# BalanceCar_CCD_Base.net
KiCad netlist of a schematic drawn in Altium Designer
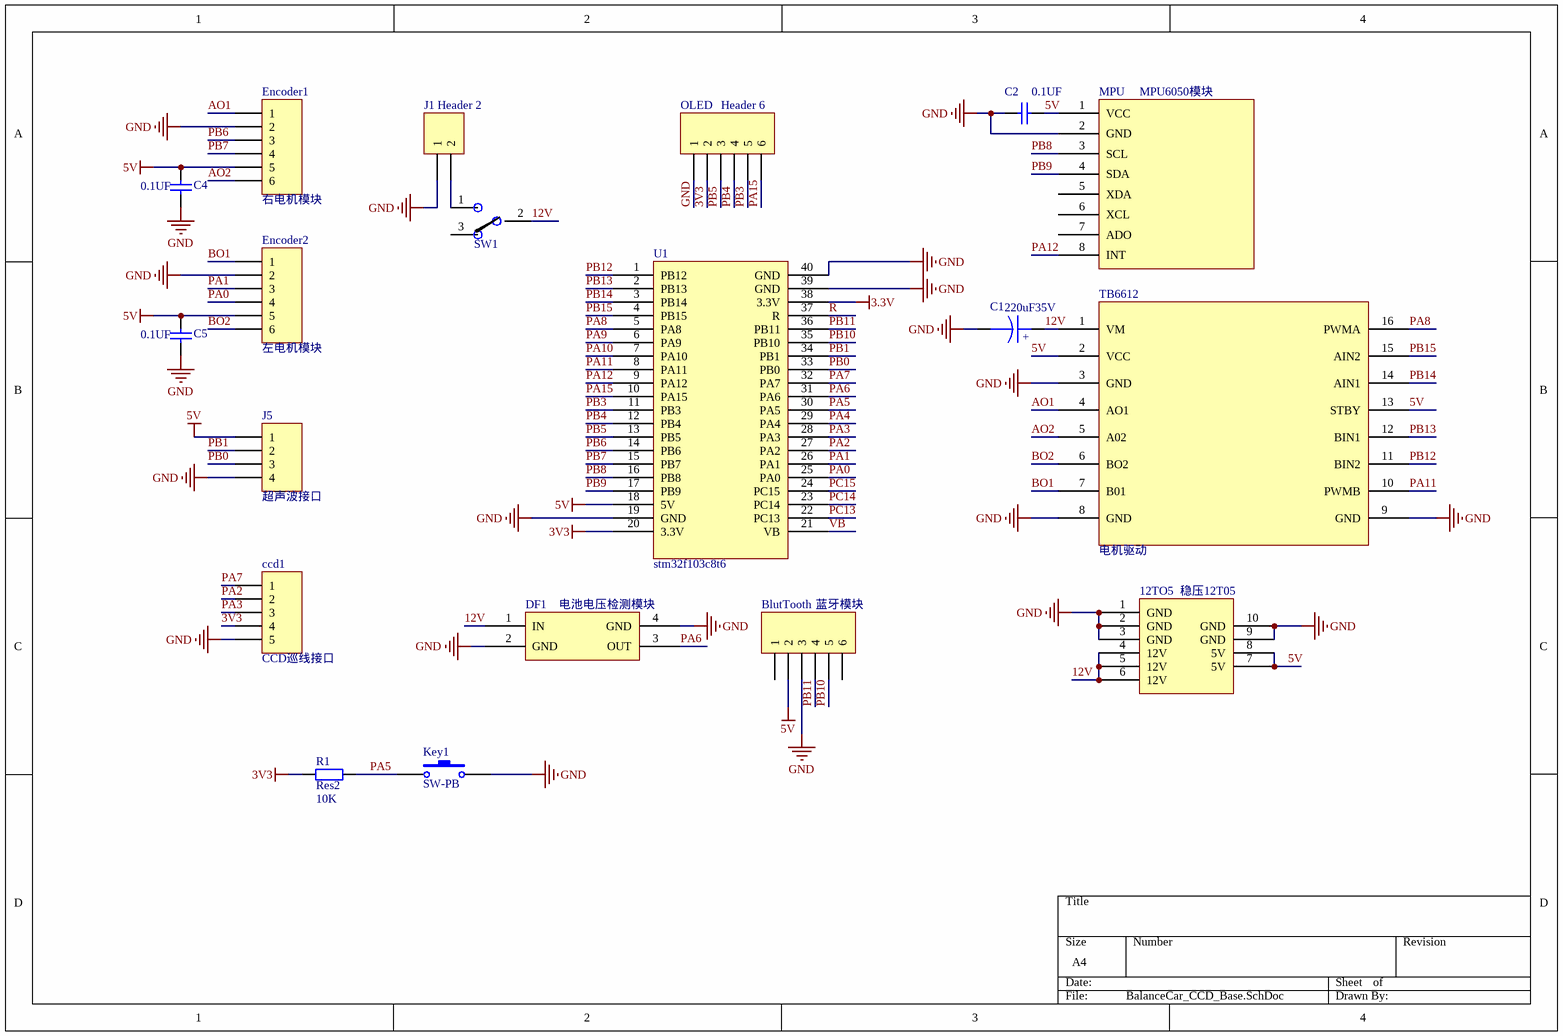
[diagram p0: BalanceCar_CCD_Base.SchDoc]

(export (version "E")
  (design (tool "Eeschema 10.0.6"))
  (components
    (comp (ref "12TO5")
      (value "稳压12T05")
      (footprint "稳压12T05")
      (libsource (lib "BalanceCar") (part "稳压12T05"))
    )
    (comp (ref "BlutTooth")
      (value "蓝牙模块")
      (footprint "HDR1X6 - XH弯")
      (description "不用焊")
      (fields (field (name "PUBLISHER") "Altium Limited"))
      (libsource (lib "BalanceCar") (part "Header 6"))
    )
    (comp (ref "C1")
      (value "220uF35V")
      (footprint "CAP-820uF-6.3V")
      (description "Capacitor")
      (libsource (lib "BalanceCar") (part "CAPACITOR POL"))
    )
    (comp (ref "C2")
      (value "0.1UF")
      (footprint "Cap-CP")
      (description "Capacitor")
      (fields (field (name "PUBLISHER") "Altium Limited"))
      (libsource (lib "BalanceCar") (part "Cap"))
    )
    (comp (ref "C4")
      (value "0.1UF")
      (footprint "Cap-CP")
      (description "Capacitor")
      (fields (field (name "PUBLISHER") "Altium Limited"))
      (libsource (lib "BalanceCar") (part "Cap"))
    )
    (comp (ref "C5")
      (value "0.1UF")
      (footprint "Cap-CP")
      (description "Capacitor")
      (fields (field (name "PUBLISHER") "Altium Limited"))
      (libsource (lib "BalanceCar") (part "Cap"))
    )
    (comp (ref "ccd1")
      (value "CCD巡线接口")
      (footprint "CCD5")
      (description "Header, 5-Pin")
      (fields (field (name "PUBLISHER") "Altium Limited"))
      (libsource (lib "Miscellaneous Connectors") (part "Header 5"))
    )
    (comp (ref "DF1")
      (value "电池电压检测模块")
      (footprint "DF - 2")
      (libsource (lib "BalanceCar") (part "电阻分压测量电量"))
    )
    (comp (ref "Encoder1")
      (value "右电机模块")
      (footprint "HDR1X6 - XH弯")
      (description "不用焊")
      (fields (field (name "PUBLISHER") "Altium Limited"))
      (libsource (lib "") (part "Header 6_1"))
    )
    (comp (ref "Encoder2")
      (value "左电机模块")
      (footprint "HDR1X6 - XH弯")
      (description "不用焊")
      (fields (field (name "PUBLISHER") "Altium Limited"))
      (libsource (lib "") (part "Header 6_1"))
    )
    (comp (ref "J1")
      (value "Header 2")
      (footprint "T HEAD")
      (description "Header, 2-Pin")
      (fields (field (name "PUBLISHER") "Altium Limited"))
      (libsource (lib "BalanceCar") (part "Header 2"))
    )
    (comp (ref "J5")
      (value "超声波接口")
      (footprint "HDR1X4")
      (description "Header, 4-Pin")
      (fields (field (name "PUBLISHER") "Altium Limited"))
      (libsource (lib "BalanceCar") (part "Header 4"))
    )
    (comp (ref "Key1")
      (value "SW-PB")
      (footprint "KEY")
      (description "Switch")
      (fields (field (name "PUBLISHER") "Altium Limited"))
      (libsource (lib "Miscellaneous Devices") (part "SW-PB"))
    )
    (comp (ref "MPU")
      (value "MPU6050模块")
      (footprint "6050new")
      (libsource (lib "BalanceCar") (part "MPU6050模块"))
    )
    (comp (ref "OLED")
      (value "Header 6")
      (footprint "OLED6")
      (description "Header, 6-Pin")
      (fields (field (name "PUBLISHER") "Altium Limited"))
      (libsource (lib "Miscellaneous Connectors") (part "Header 6"))
    )
    (comp (ref "R1")
      (value "Res2")
      (footprint "AXIAL-0.4")
      (description "Resistor")
      (fields (field (name "ALTIUM_VALUE") "10K") (field (name "PUBLISHER") "Altium Limited"))
      (libsource (lib "Miscellaneous Devices") (part "Res2"))
    )
    (comp (ref "SW1")
      (value "SW-SPDT")
      (footprint "SS12d11拨动电源开关")
      (description "单刀双掷开关")
      (libsource (lib "BalanceCar") (part "SW-SPDT"))
    )
    (comp (ref "TB6612")
      (value "电机驱动")
      (footprint "TB6612DIP")
      (libsource (lib "BalanceCar") (part "TB6612"))
    )
    (comp (ref "U1")
      (value "stm32f103c8t6")
      (footprint "PCBComponent_1 - duplicate")
      (libsource (lib "PCB_Project1") (part "Component_1_1"))
    )
  )
  (nets
    (net (code "1") (name "/12V") (class "Default")
      (node (ref "12TO5") (pin "4") (pinfunction "12V_4") (pintype "passive"))
      (node (ref "12TO5") (pin "5") (pinfunction "12V_5") (pintype "passive"))
      (node (ref "12TO5") (pin "6") (pinfunction "12V_6") (pintype "passive"))
      (node (ref "C1") (pin "1") (pinfunction "1_1") (pintype "passive"))
      (node (ref "DF1") (pin "1") (pinfunction "IN_1") (pintype "passive"))
      (node (ref "SW1") (pin "2") (pinfunction "2_2") (pintype "passive"))
      (node (ref "TB6612") (pin "1") (pinfunction "VM_1") (pintype "passive"))
    )
    (net (code "2") (name "/AO1") (class "Default")
      (node (ref "Encoder1") (pin "1") (pinfunction "1_1") (pintype "passive"))
      (node (ref "TB6612") (pin "4") (pinfunction "AO1_4") (pintype "passive"))
    )
    (net (code "3") (name "/AO2") (class "Default")
      (node (ref "Encoder1") (pin "6") (pinfunction "6_6") (pintype "passive"))
      (node (ref "TB6612") (pin "5") (pinfunction "A02_5") (pintype "passive"))
    )
    (net (code "4") (name "/BO1") (class "Default")
      (node (ref "Encoder2") (pin "1") (pinfunction "1_1") (pintype "passive"))
      (node (ref "TB6612") (pin "7") (pinfunction "B01_7") (pintype "passive"))
    )
    (net (code "5") (name "/BO2") (class "Default")
      (node (ref "Encoder2") (pin "6") (pinfunction "6_6") (pintype "passive"))
      (node (ref "TB6612") (pin "6") (pinfunction "BO2_6") (pintype "passive"))
    )
    (net (code "6") (name "/PA0") (class "Default")
      (node (ref "Encoder2") (pin "4") (pinfunction "4_4") (pintype "passive"))
      (node (ref "U1") (pin "25") (pinfunction "PA0_25") (pintype "passive"))
    )
    (net (code "7") (name "/PA1") (class "Default")
      (node (ref "Encoder2") (pin "3") (pinfunction "3_3") (pintype "passive"))
      (node (ref "U1") (pin "26") (pinfunction "PA1_26") (pintype "passive"))
    )
    (net (code "8") (name "/PA2") (class "Default")
      (node (ref "U1") (pin "27") (pinfunction "PA2_27") (pintype "passive"))
      (node (ref "ccd1") (pin "2") (pinfunction "2_2") (pintype "passive"))
    )
    (net (code "9") (name "/PA3") (class "Default")
      (node (ref "U1") (pin "28") (pinfunction "PA3_28") (pintype "passive"))
      (node (ref "ccd1") (pin "3") (pinfunction "3_3") (pintype "passive"))
    )
    (net (code "10") (name "/PA4") (class "Default")
      (node (ref "U1") (pin "29") (pinfunction "PA4_29") (pintype "passive"))
    )
    (net (code "11") (name "/PA5") (class "Default")
      (node (ref "Key1") (pin "1") (pinfunction "1_1") (pintype "passive"))
      (node (ref "R1") (pin "2") (pinfunction "2_2") (pintype "passive"))
      (node (ref "U1") (pin "30") (pinfunction "PA5_30") (pintype "passive"))
    )
    (net (code "12") (name "/PA6") (class "Default")
      (node (ref "DF1") (pin "3") (pinfunction "OUT_3") (pintype "passive"))
      (node (ref "U1") (pin "31") (pinfunction "PA6_31") (pintype "passive"))
    )
    (net (code "13") (name "/PA7") (class "Default")
      (node (ref "U1") (pin "32") (pinfunction "PA7_32") (pintype "passive"))
      (node (ref "ccd1") (pin "1") (pinfunction "1_1") (pintype "passive"))
    )
    (net (code "14") (name "/PA8") (class "Default")
      (node (ref "TB6612") (pin "16") (pinfunction "PWMA_16") (pintype "passive"))
      (node (ref "U1") (pin "5") (pinfunction "PA8_5") (pintype "passive"))
    )
    (net (code "15") (name "/PA9") (class "Default")
      (node (ref "U1") (pin "6") (pinfunction "PA9_6") (pintype "passive"))
    )
    (net (code "16") (name "/PA10") (class "Default")
      (node (ref "U1") (pin "7") (pinfunction "PA10_7") (pintype "passive"))
    )
    (net (code "17") (name "/PA11") (class "Default")
      (node (ref "TB6612") (pin "10") (pinfunction "PWMB_10") (pintype "passive"))
      (node (ref "U1") (pin "8") (pinfunction "PA11_8") (pintype "passive"))
    )
    (net (code "18") (name "/PA12") (class "Default")
      (node (ref "MPU") (pin "8") (pinfunction "INT_8") (pintype "passive"))
      (node (ref "U1") (pin "9") (pinfunction "PA12_9") (pintype "passive"))
    )
    (net (code "19") (name "/PA15") (class "Default")
      (node (ref "OLED") (pin "6") (pinfunction "6_6") (pintype "passive"))
      (node (ref "U1") (pin "10") (pinfunction "PA15_10") (pintype "passive"))
    )
    (net (code "20") (name "/PB0") (class "Default")
      (node (ref "J5") (pin "3") (pinfunction "3_3") (pintype "passive"))
      (node (ref "U1") (pin "33") (pinfunction "PB0_33") (pintype "passive"))
    )
    (net (code "21") (name "/PB1") (class "Default")
      (node (ref "J5") (pin "2") (pinfunction "2_2") (pintype "passive"))
      (node (ref "U1") (pin "34") (pinfunction "PB1_34") (pintype "passive"))
    )
    (net (code "22") (name "/PB3") (class "Default")
      (node (ref "OLED") (pin "5") (pinfunction "5_5") (pintype "passive"))
      (node (ref "U1") (pin "11") (pinfunction "PB3_11") (pintype "passive"))
    )
    (net (code "23") (name "/PB4") (class "Default")
      (node (ref "OLED") (pin "4") (pinfunction "4_4") (pintype "passive"))
      (node (ref "U1") (pin "12") (pinfunction "PB4_12") (pintype "passive"))
    )
    (net (code "24") (name "/PB5") (class "Default")
      (node (ref "OLED") (pin "3") (pinfunction "3_3") (pintype "passive"))
      (node (ref "U1") (pin "13") (pinfunction "PB5_13") (pintype "passive"))
    )
    (net (code "25") (name "/PB6") (class "Default")
      (node (ref "Encoder1") (pin "3") (pinfunction "3_3") (pintype "passive"))
      (node (ref "U1") (pin "14") (pinfunction "PB6_14") (pintype "passive"))
    )
    (net (code "26") (name "/PB7") (class "Default")
      (node (ref "Encoder1") (pin "4") (pinfunction "4_4") (pintype "passive"))
      (node (ref "U1") (pin "15") (pinfunction "PB7_15") (pintype "passive"))
    )
    (net (code "27") (name "/PB8") (class "Default")
      (node (ref "MPU") (pin "3") (pinfunction "SCL_3") (pintype "passive"))
      (node (ref "U1") (pin "16") (pinfunction "PB8_16") (pintype "passive"))
    )
    (net (code "28") (name "/PB9") (class "Default")
      (node (ref "MPU") (pin "4") (pinfunction "SDA_4") (pintype "passive"))
      (node (ref "U1") (pin "17") (pinfunction "PB9_17") (pintype "passive"))
    )
    (net (code "29") (name "/PB10") (class "Default")
      (node (ref "BlutTooth") (pin "5") (pinfunction "5_5") (pintype "passive"))
      (node (ref "U1") (pin "35") (pinfunction "PB10_35") (pintype "passive"))
    )
    (net (code "30") (name "/PB11") (class "Default")
      (node (ref "BlutTooth") (pin "4") (pinfunction "4_4") (pintype "passive"))
      (node (ref "U1") (pin "36") (pinfunction "PB11_36") (pintype "passive"))
    )
    (net (code "31") (name "/PB12") (class "Default")
      (node (ref "TB6612") (pin "11") (pinfunction "BIN2_11") (pintype "passive"))
      (node (ref "U1") (pin "1") (pinfunction "PB12_1") (pintype "passive"))
    )
    (net (code "32") (name "/PB13") (class "Default")
      (node (ref "TB6612") (pin "12") (pinfunction "BIN1_12") (pintype "passive"))
      (node (ref "U1") (pin "2") (pinfunction "PB13_2") (pintype "passive"))
    )
    (net (code "33") (name "/PB14") (class "Default")
      (node (ref "TB6612") (pin "14") (pinfunction "AIN1_14") (pintype "passive"))
      (node (ref "U1") (pin "3") (pinfunction "PB14_3") (pintype "passive"))
    )
    (net (code "34") (name "/PB15") (class "Default")
      (node (ref "TB6612") (pin "15") (pinfunction "AIN2_15") (pintype "passive"))
      (node (ref "U1") (pin "4") (pinfunction "PB15_4") (pintype "passive"))
    )
    (net (code "35") (name "/PC13") (class "Default")
      (node (ref "U1") (pin "22") (pinfunction "PC13_22") (pintype "passive"))
    )
    (net (code "36") (name "/PC14") (class "Default")
      (node (ref "U1") (pin "23") (pinfunction "PC14_23") (pintype "passive"))
    )
    (net (code "37") (name "/PC15") (class "Default")
      (node (ref "U1") (pin "24") (pinfunction "PC15_24") (pintype "passive"))
    )
    (net (code "38") (name "/R") (class "Default")
      (node (ref "U1") (pin "37") (pinfunction "R_37") (pintype "passive"))
    )
    (net (code "39") (name "/VB") (class "Default")
      (node (ref "U1") (pin "21") (pinfunction "VB_21") (pintype "passive"))
    )
    (net (code "40") (name "3.3V") (class "Default")
      (node (ref "U1") (pin "38") (pinfunction "3.3V_38") (pintype "passive"))
    )
    (net (code "41") (name "3V3") (class "Default")
      (node (ref "OLED") (pin "2") (pinfunction "2_2") (pintype "passive"))
      (node (ref "R1") (pin "1") (pinfunction "1_1") (pintype "passive"))
      (node (ref "U1") (pin "20") (pinfunction "3.3V_20") (pintype "passive"))
      (node (ref "ccd1") (pin "4") (pinfunction "4_4") (pintype "passive"))
    )
    (net (code "42") (name "5V") (class "Default")
      (node (ref "12TO5") (pin "7") (pinfunction "5V_7") (pintype "passive"))
      (node (ref "12TO5") (pin "8") (pinfunction "5V_8") (pintype "passive"))
      (node (ref "BlutTooth") (pin "2") (pinfunction "2_2") (pintype "passive"))
      (node (ref "C2") (pin "2") (pinfunction "2_2") (pintype "passive"))
      (node (ref "C4") (pin "2") (pinfunction "2_2") (pintype "passive"))
      (node (ref "C5") (pin "2") (pinfunction "2_2") (pintype "passive"))
      (node (ref "Encoder1") (pin "5") (pinfunction "5_5") (pintype "passive"))
      (node (ref "Encoder2") (pin "5") (pinfunction "5_5") (pintype "passive"))
      (node (ref "J5") (pin "1") (pinfunction "1_1") (pintype "passive"))
      (node (ref "MPU") (pin "1") (pinfunction "VCC_1") (pintype "passive"))
      (node (ref "TB6612") (pin "13") (pinfunction "STBY_13") (pintype "passive"))
      (node (ref "TB6612") (pin "2") (pinfunction "VCC_2") (pintype "passive"))
      (node (ref "U1") (pin "18") (pinfunction "5V_18") (pintype "passive"))
    )
    (net (code "43") (name "GND") (class "Default")
      (node (ref "12TO5") (pin "1") (pinfunction "GND_1") (pintype "passive"))
      (node (ref "12TO5") (pin "10") (pinfunction "GND_10") (pintype "passive"))
      (node (ref "12TO5") (pin "2") (pinfunction "GND_2") (pintype "passive"))
      (node (ref "12TO5") (pin "3") (pinfunction "GND_3") (pintype "passive"))
      (node (ref "12TO5") (pin "9") (pinfunction "GND_9") (pintype "passive"))
      (node (ref "BlutTooth") (pin "3") (pinfunction "3_3") (pintype "passive"))
      (node (ref "C1") (pin "2") (pinfunction "2_2") (pintype "passive"))
      (node (ref "C2") (pin "1") (pinfunction "1_1") (pintype "passive"))
      (node (ref "C4") (pin "1") (pinfunction "1_1") (pintype "passive"))
      (node (ref "C5") (pin "1") (pinfunction "1_1") (pintype "passive"))
      (node (ref "DF1") (pin "2") (pinfunction "GND_2") (pintype "passive"))
      (node (ref "DF1") (pin "4") (pinfunction "GND_4") (pintype "passive"))
      (node (ref "Encoder1") (pin "2") (pinfunction "2_2") (pintype "passive"))
      (node (ref "Encoder2") (pin "2") (pinfunction "2_2") (pintype "passive"))
      (node (ref "J1") (pin "1") (pinfunction "1_1") (pintype "passive"))
      (node (ref "J5") (pin "4") (pinfunction "4_4") (pintype "passive"))
      (node (ref "Key1") (pin "2") (pinfunction "2_2") (pintype "passive"))
      (node (ref "MPU") (pin "2") (pinfunction "GND_2") (pintype "passive"))
      (node (ref "OLED") (pin "1") (pinfunction "1_1") (pintype "passive"))
      (node (ref "TB6612") (pin "3") (pinfunction "GND_3") (pintype "passive"))
      (node (ref "TB6612") (pin "8") (pinfunction "GND_8") (pintype "passive"))
      (node (ref "TB6612") (pin "9") (pinfunction "GND_9") (pintype "passive"))
      (node (ref "U1") (pin "19") (pinfunction "GND_19") (pintype "passive"))
      (node (ref "U1") (pin "39") (pinfunction "GND_39") (pintype "passive"))
      (node (ref "U1") (pin "40") (pinfunction "GND_40") (pintype "passive"))
      (node (ref "ccd1") (pin "5") (pinfunction "5_5") (pintype "passive"))
    )
    (net (code "44") (name "Net-(J1-Pad2)") (class "Default")
      (node (ref "J1") (pin "2") (pinfunction "2_2") (pintype "passive"))
      (node (ref "SW1") (pin "1") (pinfunction "1_1") (pintype "passive"))
    )
    (net (code "45") (name "unconnected-(BlutTooth-Pad1)") (class "Default")
      (node (ref "BlutTooth") (pin "1") (pinfunction "1_1") (pintype "passive"))
    )
    (net (code "46") (name "unconnected-(BlutTooth-Pad6)") (class "Default")
      (node (ref "BlutTooth") (pin "6") (pinfunction "6_6") (pintype "passive"))
    )
    (net (code "47") (name "unconnected-(MPU-ADO-Pad7)") (class "Default")
      (node (ref "MPU") (pin "7") (pinfunction "ADO_7") (pintype "passive"))
    )
    (net (code "48") (name "unconnected-(MPU-XCL-Pad6)") (class "Default")
      (node (ref "MPU") (pin "6") (pinfunction "XCL_6") (pintype "passive"))
    )
    (net (code "49") (name "unconnected-(MPU-XDA-Pad5)") (class "Default")
      (node (ref "MPU") (pin "5") (pinfunction "XDA_5") (pintype "passive"))
    )
    (net (code "50") (name "unconnected-(SW1-Pad3)") (class "Default")
      (node (ref "SW1") (pin "3") (pinfunction "3_3") (pintype "passive"))
    )
  )
)
